# DCDC_Top.net
KiCad netlist of a schematic drawn in Altium Designer
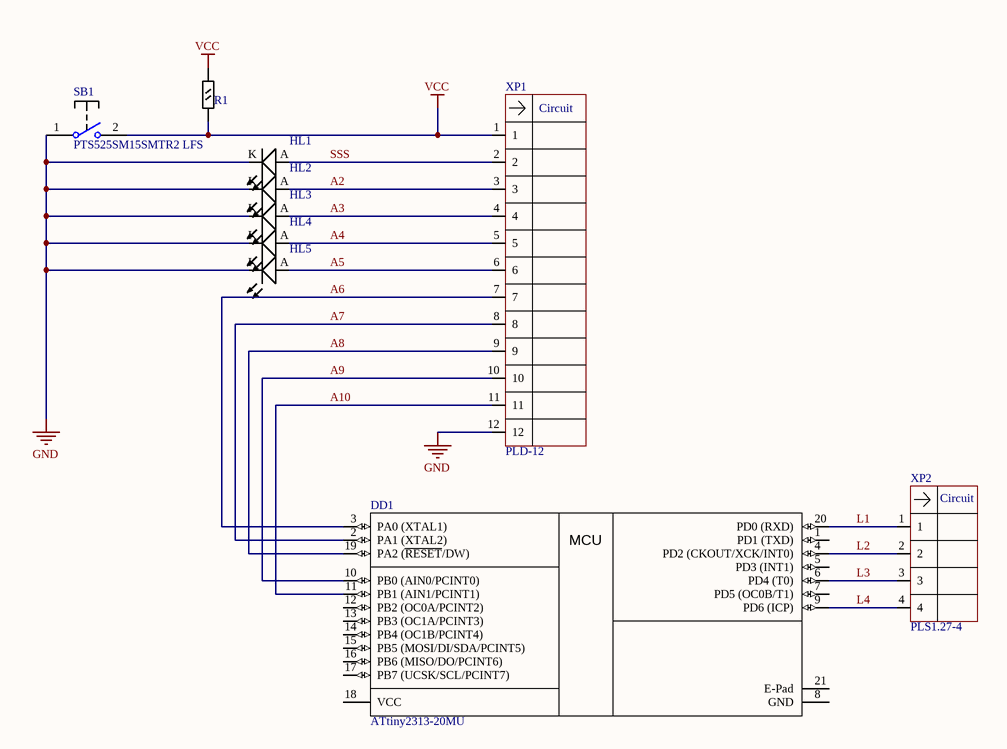
[diagram p0: DCDC_Top.SchDoc]

(export (version "E")
  (design (tool "Eeschema 10.0.6"))
  (components
    (comp (ref "DD1")
      (value "ATtiny2313-20MU")
      (footprint "20M1_M")
      (fields (field (name "PUBLISHER") "Altium Limited"))
      (libsource (lib "SssAccesDatbase") (part "ATtiny2313-20MU"))
    )
    (comp (ref "HL1")
      (value "GR-0603")
      (footprint "LED-0603-GREEN")
      (description "LED GREEN DIFFUSED 0603 SMD")
      (fields
        (field (name "PART NUMBER") "150060VS55040")
        (field (name "DIGI-KEY PART NUMBER") "732-12017-1-ND")
      )
      (libsource (lib "SssAccesDatbase") (part "LED_AK"))
    )
    (comp (ref "HL2")
      (value "GR-0603")
      (footprint "LED-0603-GREEN")
      (description "LED GREEN DIFFUSED 0603 SMD")
      (fields
        (field (name "PART NUMBER") "150060VS55040")
        (field (name "DIGI-KEY PART NUMBER") "732-12017-1-ND")
      )
      (libsource (lib "SssAccesDatbase") (part "LED_AK"))
    )
    (comp (ref "HL3")
      (value "GR-0603")
      (footprint "LED-0603-GREEN")
      (description "LED GREEN DIFFUSED 0603 SMD")
      (fields
        (field (name "PART NUMBER") "150060VS55040")
        (field (name "DIGI-KEY PART NUMBER") "732-12017-1-ND")
      )
      (libsource (lib "SssAccesDatbase") (part "LED_AK"))
    )
    (comp (ref "HL4")
      (value "GR-0603")
      (footprint "LED-0603-GREEN")
      (description "LED GREEN DIFFUSED 0603 SMD")
      (fields
        (field (name "PART NUMBER") "150060VS55040")
        (field (name "DIGI-KEY PART NUMBER") "732-12017-1-ND")
      )
      (libsource (lib "SssAccesDatbase") (part "LED_AK"))
    )
    (comp (ref "HL5")
      (value "GR-0603")
      (footprint "LED-0603-GREEN")
      (description "LED GREEN DIFFUSED 0603 SMD")
      (fields
        (field (name "PART NUMBER") "150060VS55040")
        (field (name "DIGI-KEY PART NUMBER") "732-12017-1-ND")
      )
      (libsource (lib "SssAccesDatbase") (part "LED_AK"))
    )
    (comp (ref "R1")
      (value "1k 1%")
      (footprint "1206")
      (description "RES SMD 1K ohm 1% 200V AEC-Q200")
      (fields
        (field (name "PART NUMBER") "AA1206FR-071KL")
        (field (name "MOUSER PART NUMBER") "603-AA1206FR-071KL")
      )
      (libsource (lib "SssAccesDatbase") (part "Resistor 0,125W"))
    )
    (comp (ref "SB1")
      (value "PTS525SM15SMTR2 LFS")
      (footprint "TACT_SWITCH KPT1187B")
      (description "SWITCH TACTILE SPST-NO 0.02A 15V")
      (fields (field (name "DIGI-KEY PART NUMBER") "CKN9104CT-ND"))
      (libsource (lib "SssAccesDatbase") (part "TACT_SWITCH KPT1187B"))
    )
    (comp (ref "XP1")
      (value "PLD-12")
      (footprint "PLD-12-3D")
      (libsource (lib "SssAccesDatbase") (part "XP-12"))
    )
    (comp (ref "XP2")
      (value "PLS1.27-4")
      (footprint "PLLS1.27-4")
      (libsource (lib "SssAccesDatbase") (part "XP-4"))
    )
  )
  (nets
    (net (code "1") (name "/A2") (class "Default")
      (node (ref "HL2") (pin "A") (pinfunction "A_A") (pintype "passive"))
      (node (ref "XP1") (pin "3") (pinfunction "3_3") (pintype "passive"))
    )
    (net (code "2") (name "/A3") (class "Default")
      (node (ref "HL3") (pin "A") (pinfunction "A_A") (pintype "passive"))
      (node (ref "XP1") (pin "4") (pinfunction "4_4") (pintype "passive"))
    )
    (net (code "3") (name "/A4") (class "Default")
      (node (ref "HL4") (pin "A") (pinfunction "A_A") (pintype "passive"))
      (node (ref "XP1") (pin "5") (pinfunction "5_5") (pintype "passive"))
    )
    (net (code "4") (name "/A5") (class "Default")
      (node (ref "HL5") (pin "A") (pinfunction "A_A") (pintype "passive"))
      (node (ref "XP1") (pin "6") (pinfunction "6_6") (pintype "passive"))
    )
    (net (code "5") (name "/A6") (class "Default")
      (node (ref "DD1") (pin "3") (pinfunction "PA0_(XTAL1)_3") (pintype "bidirectional"))
      (node (ref "XP1") (pin "7") (pinfunction "7_7") (pintype "passive"))
    )
    (net (code "6") (name "/A7") (class "Default")
      (node (ref "DD1") (pin "2") (pinfunction "PA1_(XTAL2)_2") (pintype "bidirectional"))
      (node (ref "XP1") (pin "8") (pinfunction "8_8") (pintype "passive"))
    )
    (net (code "7") (name "/A8") (class "Default")
      (node (ref "DD1") (pin "19") (pinfunction "PA2_(~{RESET}/DW)_19") (pintype "bidirectional"))
      (node (ref "XP1") (pin "9") (pinfunction "9_9") (pintype "passive"))
    )
    (net (code "8") (name "/A9") (class "Default")
      (node (ref "DD1") (pin "10") (pinfunction "PB0_(AIN0/PCINT0)_10") (pintype "bidirectional"))
      (node (ref "XP1") (pin "10") (pinfunction "10_10") (pintype "passive"))
    )
    (net (code "9") (name "/A10") (class "Default")
      (node (ref "DD1") (pin "11") (pinfunction "PB1_(AIN1/PCINT1)_11") (pintype "bidirectional"))
      (node (ref "XP1") (pin "11") (pinfunction "11_11") (pintype "passive"))
    )
    (net (code "10") (name "/L1") (class "Default")
      (node (ref "DD1") (pin "20") (pinfunction "PD0_(RXD)_20") (pintype "bidirectional"))
      (node (ref "XP2") (pin "1") (pinfunction "1_1") (pintype "passive"))
    )
    (net (code "11") (name "/L2") (class "Default")
      (node (ref "DD1") (pin "4") (pinfunction "PD2_(CKOUT/XCK/INT0)_4") (pintype "bidirectional"))
      (node (ref "XP2") (pin "2") (pinfunction "2_2") (pintype "passive"))
    )
    (net (code "12") (name "/L3") (class "Default")
      (node (ref "DD1") (pin "6") (pinfunction "PD4_(T0)_6") (pintype "bidirectional"))
      (node (ref "XP2") (pin "3") (pinfunction "3_3") (pintype "passive"))
    )
    (net (code "13") (name "/L4") (class "Default")
      (node (ref "DD1") (pin "9") (pinfunction "PD6_(ICP)_9") (pintype "bidirectional"))
      (node (ref "XP2") (pin "4") (pinfunction "4_4") (pintype "passive"))
    )
    (net (code "14") (name "/SSS") (class "Default")
      (node (ref "HL1") (pin "A") (pinfunction "A_A") (pintype "passive"))
      (node (ref "XP1") (pin "2") (pinfunction "2_2") (pintype "passive"))
    )
    (net (code "15") (name "GND") (class "Default")
      (node (ref "HL1") (pin "K") (pinfunction "K_K") (pintype "passive"))
      (node (ref "HL2") (pin "K") (pinfunction "K_K") (pintype "passive"))
      (node (ref "HL3") (pin "K") (pinfunction "K_K") (pintype "passive"))
      (node (ref "HL4") (pin "K") (pinfunction "K_K") (pintype "passive"))
      (node (ref "HL5") (pin "K") (pinfunction "K_K") (pintype "passive"))
      (node (ref "SB1") (pin "1") (pinfunction "COMMON_1") (pintype "passive"))
      (node (ref "XP1") (pin "12") (pinfunction "12_12") (pintype "passive"))
    )
    (net (code "16") (name "VCC") (class "Default")
      (node (ref "R1") (pin "1") (pinfunction "1_1") (pintype "passive"))
      (node (ref "R1") (pin "2") (pinfunction "2_2") (pintype "passive"))
      (node (ref "SB1") (pin "2") (pinfunction "NO_2") (pintype "passive"))
      (node (ref "XP1") (pin "1") (pinfunction "1_1") (pintype "passive"))
    )
    (net (code "17") (name "unconnected-(DD1-E-Pad-Pad21)") (class "Default")
      (node (ref "DD1") (pin "21") (pinfunction "E-Pad_21") (pintype "power_in"))
    )
    (net (code "18") (name "unconnected-(DD1-GND-Pad8)") (class "Default")
      (node (ref "DD1") (pin "8") (pinfunction "GND_8") (pintype "power_in"))
    )
    (net (code "19") (name "unconnected-(DD1-PB2_(OC0A{slash}PCINT2)-Pad12)") (class "Default")
      (node (ref "DD1") (pin "12") (pinfunction "PB2_(OC0A/PCINT2)_12") (pintype "bidirectional"))
    )
    (net (code "20") (name "unconnected-(DD1-PB3_(OC1A{slash}PCINT3)-Pad13)") (class "Default")
      (node (ref "DD1") (pin "13") (pinfunction "PB3_(OC1A/PCINT3)_13") (pintype "bidirectional"))
    )
    (net (code "21") (name "unconnected-(DD1-PB4_(OC1B{slash}PCINT4)-Pad14)") (class "Default")
      (node (ref "DD1") (pin "14") (pinfunction "PB4_(OC1B/PCINT4)_14") (pintype "bidirectional"))
    )
    (net (code "22") (name "unconnected-(DD1-PB5_(MOSI{slash}DI{slash}SDA{slash}PCINT5)-Pad15)") (class "Default")
      (node (ref "DD1") (pin "15") (pinfunction "PB5_(MOSI/DI/SDA/PCINT5)_15") (pintype "bidirectional"))
    )
    (net (code "23") (name "unconnected-(DD1-PB6_(MISO{slash}DO{slash}PCINT6)-Pad16)") (class "Default")
      (node (ref "DD1") (pin "16") (pinfunction "PB6_(MISO/DO/PCINT6)_16") (pintype "bidirectional"))
    )
    (net (code "24") (name "unconnected-(DD1-PB7_(UCSK{slash}SCL{slash}PCINT7)-Pad17)") (class "Default")
      (node (ref "DD1") (pin "17") (pinfunction "PB7_(UCSK/SCL/PCINT7)_17") (pintype "bidirectional"))
    )
    (net (code "25") (name "unconnected-(DD1-PD1_(TXD)-Pad1)") (class "Default")
      (node (ref "DD1") (pin "1") (pinfunction "PD1_(TXD)_1") (pintype "bidirectional"))
    )
    (net (code "26") (name "unconnected-(DD1-PD3_(INT1)-Pad5)") (class "Default")
      (node (ref "DD1") (pin "5") (pinfunction "PD3_(INT1)_5") (pintype "bidirectional"))
    )
    (net (code "27") (name "unconnected-(DD1-PD5_(OC0B{slash}T1)-Pad7)") (class "Default")
      (node (ref "DD1") (pin "7") (pinfunction "PD5_(OC0B/T1)_7") (pintype "bidirectional"))
    )
    (net (code "28") (name "unconnected-(DD1-VCC-Pad18)") (class "Default")
      (node (ref "DD1") (pin "18") (pinfunction "VCC_18") (pintype "power_in"))
    )
  )
)
